# motorController.net
KiCad netlist of a schematic drawn in EAGLE
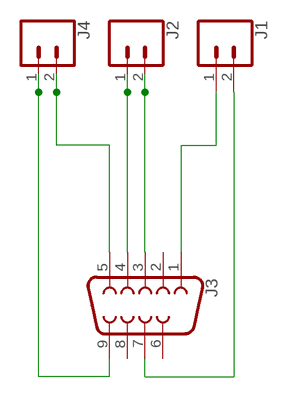
[diagram p0: schematic, sheet 1]

(export (version "E")
  (design (tool "Eeschema 10.0.6"))
  (components
    (comp (ref "J1")
      (value "CONN_025MM")
      (footprint "eagle-import:SCREWTERMINAL-5MM-2")
      (libsource (lib "eagle-import") (part "CONN_025MM"))
    )
    (comp (ref "J2")
      (value "CONN_025MM")
      (footprint "eagle-import:SCREWTERMINAL-5MM-2")
      (libsource (lib "eagle-import") (part "CONN_025MM"))
    )
    (comp (ref "J3")
      (value "DB9FEMALE")
      (footprint "eagle-import:DB9")
      (libsource (lib "eagle-import") (part "DB9FEMALE"))
    )
    (comp (ref "J4")
      (value "CONN_025MM")
      (footprint "eagle-import:SCREWTERMINAL-5MM-2")
      (libsource (lib "eagle-import") (part "CONN_025MM"))
    )
  )
  (nets
    (net (code "1") (name "Net-(J1-Pad1)") (class "Default")
      (node (ref "J1") (pin "1") (pinfunction "1_1") (pintype "passive"))
      (node (ref "J3") (pin "1") (pinfunction "1_1") (pintype "passive"))
    )
    (net (code "2") (name "Net-(J1-Pad2)") (class "Default")
      (node (ref "J1") (pin "2") (pinfunction "2_2") (pintype "passive"))
      (node (ref "J3") (pin "7") (pinfunction "7_7") (pintype "passive"))
    )
    (net (code "3") (name "Net-(J2-Pad1)") (class "Default")
      (node (ref "J2") (pin "1") (pinfunction "1_1") (pintype "passive"))
      (node (ref "J3") (pin "4") (pinfunction "4_4") (pintype "passive"))
    )
    (net (code "4") (name "Net-(J2-Pad2)") (class "Default")
      (node (ref "J2") (pin "2") (pinfunction "2_2") (pintype "passive"))
      (node (ref "J3") (pin "3") (pinfunction "3_3") (pintype "passive"))
    )
    (net (code "5") (name "Net-(J3-Pad5)") (class "Default")
      (node (ref "J3") (pin "5") (pinfunction "5_5") (pintype "passive"))
      (node (ref "J4") (pin "2") (pinfunction "2_2") (pintype "passive"))
    )
    (net (code "6") (name "Net-(J3-Pad9)") (class "Default")
      (node (ref "J3") (pin "9") (pinfunction "9_9") (pintype "passive"))
      (node (ref "J4") (pin "1") (pinfunction "1_1") (pintype "passive"))
    )
    (net (code "7") (name "unconnected-(J3-Pad2)") (class "Default")
      (node (ref "J3") (pin "2") (pinfunction "2_2") (pintype "passive"))
    )
    (net (code "8") (name "unconnected-(J3-Pad6)") (class "Default")
      (node (ref "J3") (pin "6") (pinfunction "6_6") (pintype "passive"))
    )
    (net (code "9") (name "unconnected-(J3-Pad8)") (class "Default")
      (node (ref "J3") (pin "8") (pinfunction "8_8") (pintype "passive"))
    )
  )
)
